# battery_monitor_6803-2_Rev4.net
KiCad netlist of a schematic drawn in EAGLE
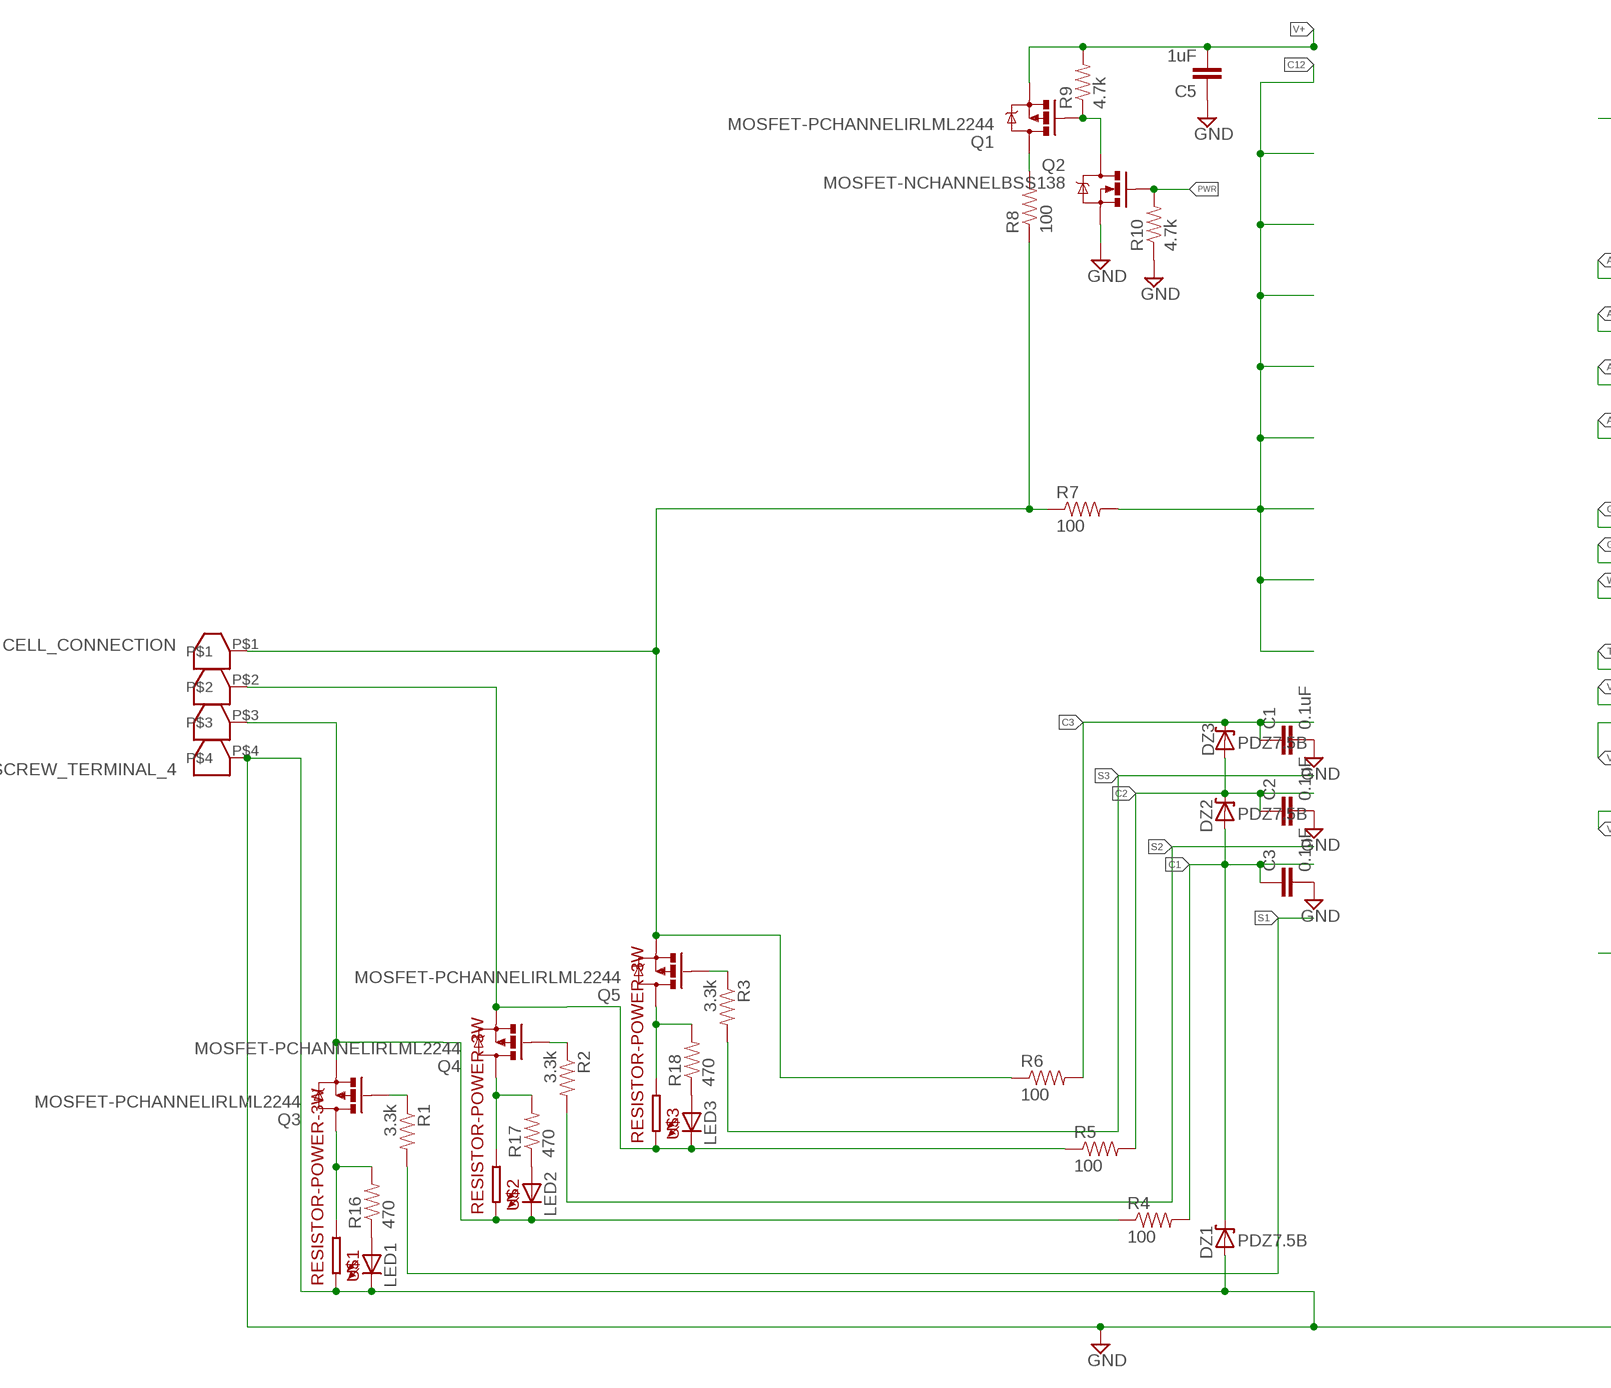
[diagram p0: schematic, sheet 1, part 1 of 2]
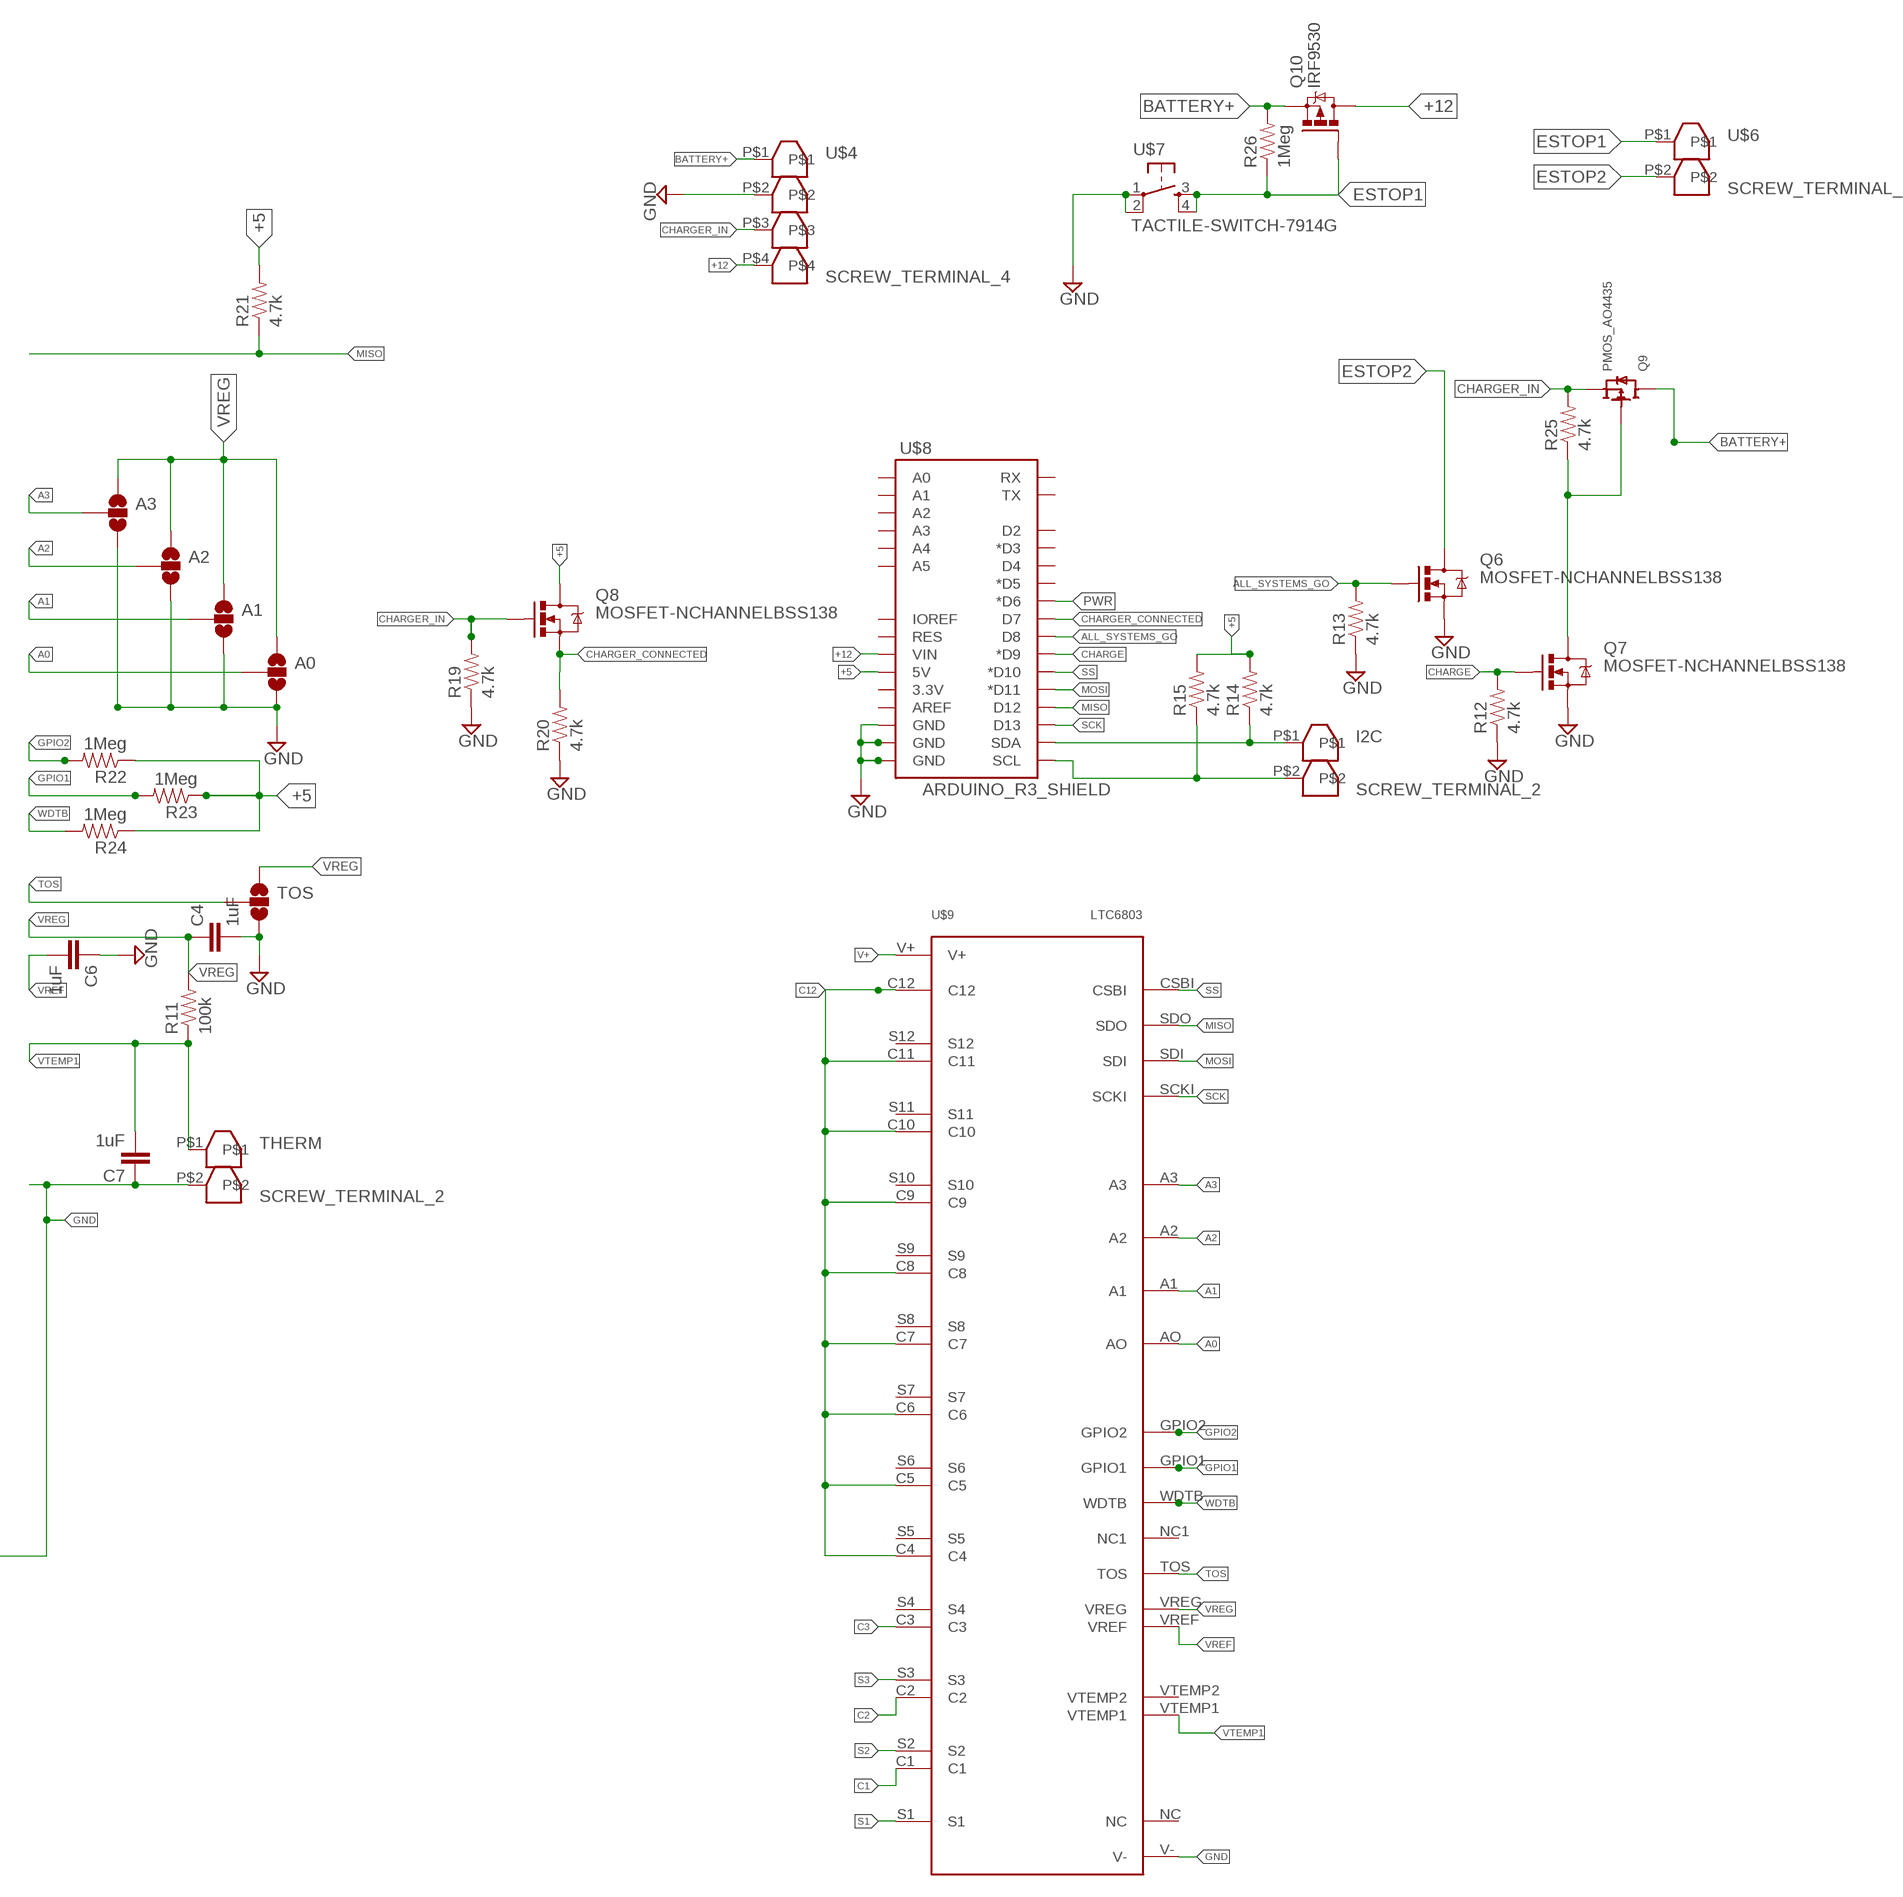
[diagram p1: schematic, sheet 1, part 2 of 2]

(export (version "E")
  (design (tool "Eeschema 10.0.6"))
  (components
    (comp (ref "A0")
      (value "SOLDERJUMPER_2WAYS")
      (footprint "eagle-import:SJ_3")
      (libsource (lib "eagle-import") (part "SOLDERJUMPER_2WAYS"))
    )
    (comp (ref "A1")
      (value "SOLDERJUMPER_2WAYS")
      (footprint "eagle-import:SJ_3")
      (libsource (lib "eagle-import") (part "SOLDERJUMPER_2WAYS"))
    )
    (comp (ref "A2")
      (value "SOLDERJUMPER_2WAYS")
      (footprint "eagle-import:SJ_3")
      (libsource (lib "eagle-import") (part "SOLDERJUMPER_2WAYS"))
    )
    (comp (ref "A3")
      (value "SOLDERJUMPER_2WAYS")
      (footprint "eagle-import:SJ_3")
      (libsource (lib "eagle-import") (part "SOLDERJUMPER_2WAYS"))
    )
    (comp (ref "C1")
      (value "0.1uF")
      (footprint "eagle-import:0603-CAP")
      (fields (field (name "MF") "AVX CORPORATION") (field (name "MPN") "0603YG104ZAT2A"))
      (libsource (lib "eagle-import") (part "0.1UF-100V-10%(0603)"))
    )
    (comp (ref "C2")
      (value "0.1uF")
      (footprint "eagle-import:0603-CAP")
      (fields (field (name "MF") "AVX CORPORATION") (field (name "MPN") "0603YG104ZAT2A"))
      (libsource (lib "eagle-import") (part "0.1UF-100V-10%(0603)"))
    )
    (comp (ref "C3")
      (value "0.1uF")
      (footprint "eagle-import:0603-CAP")
      (fields (field (name "MF") "AVX CORPORATION") (field (name "MPN") "0603YG104ZAT2A"))
      (libsource (lib "eagle-import") (part "0.1UF-100V-10%(0603)"))
    )
    (comp (ref "C4")
      (value "1uF")
      (footprint "eagle-import:0603-CAP")
      (fields (field (name "MPN") "C0603X5R0J105M030BC") (field (name "PROD_ID") "CAP-08390"))
      (libsource (lib "eagle-import") (part "0.1UF-100V-10%(0603)"))
    )
    (comp (ref "C5")
      (value "1uF")
      (footprint "eagle-import:0603-CAP")
      (fields (field (name "MPN") "C0603X5R0J105M030BC") (field (name "PROD_ID") "CAP-08390"))
      (libsource (lib "eagle-import") (part "0.1UF-100V-10%(0603)"))
    )
    (comp (ref "C6")
      (value "1uF")
      (footprint "eagle-import:0603-CAP")
      (fields (field (name "MPN") "C0603X5R0J105M030BC") (field (name "PROD_ID") "CAP-08390"))
      (libsource (lib "eagle-import") (part "0.1UF-100V-10%(0603)"))
    )
    (comp (ref "C7")
      (value "1uF")
      (footprint "eagle-import:0603-CAP")
      (fields (field (name "MPN") "C0603X5R0J105M030BC") (field (name "PROD_ID") "CAP-08390"))
      (libsource (lib "eagle-import") (part "0.1UF-100V-10%(0603)"))
    )
    (comp (ref "CELL_CONNECTION")
      (value "SCREW_TERMINAL_4")
      (footprint "eagle-import:SCREW_TERMINAL_4")
      (fields (field (name "MF") "TYCO ELECTRONICS") (field (name "MPN") "282834-4"))
      (libsource (lib "eagle-import") (part "SCREW_TERMINAL_4"))
    )
    (comp (ref "DZ1")
      (value "PDZ7.5B")
      (footprint "eagle-import:SOD-323")
      (fields (field (name "MPN") "PDZ7.5B,115"))
      (libsource (lib "eagle-import") (part "DIODE-ZENER-BZT52"))
    )
    (comp (ref "DZ2")
      (value "PDZ7.5B")
      (footprint "eagle-import:SOD-323")
      (fields (field (name "MPN") "PDZ7.5B,115"))
      (libsource (lib "eagle-import") (part "DIODE-ZENER-BZT52"))
    )
    (comp (ref "DZ3")
      (value "PDZ7.5B")
      (footprint "eagle-import:SOD-323")
      (fields (field (name "MPN") "PDZ7.5B,115"))
      (libsource (lib "eagle-import") (part "DIODE-ZENER-BZT52"))
    )
    (comp (ref "I2C")
      (value "SCREW_TERMINAL_2")
      (footprint "eagle-import:SCREW_TERMINAL_2")
      (fields (field (name "MF") "TYCO ELECTRONICS") (field (name "MPN") "282834-2"))
      (libsource (lib "eagle-import") (part "isaac1_SCREW_TERMINAL_2"))
    )
    (comp (ref "LED1")
      (value "LED0603")
      (footprint "eagle-import:LED-0603")
      (fields (field (name "MPN") "150060RS75000"))
      (libsource (lib "eagle-import") (part "LED0603"))
    )
    (comp (ref "LED2")
      (value "LED0603")
      (footprint "eagle-import:LED-0603")
      (fields (field (name "MPN") "150060RS75000"))
      (libsource (lib "eagle-import") (part "LED0603"))
    )
    (comp (ref "LED3")
      (value "LED0603")
      (footprint "eagle-import:LED-0603")
      (fields (field (name "MPN") "150060RS75000"))
      (libsource (lib "eagle-import") (part "LED0603"))
    )
    (comp (ref "Q1")
      (value "MOSFET-PCHANNELIRLML2244")
      (footprint "eagle-import:SOT23-3")
      (fields (field (name "MPN") "IRLML2244TRPBF"))
      (libsource (lib "eagle-import") (part "MOSFET-PCHANNELIRLML2244"))
    )
    (comp (ref "Q2")
      (value "MOSFET-NCHANNELBSS138")
      (footprint "eagle-import:SOT23")
      (fields (field (name "MPN") "IRLML0030TRPBF"))
      (libsource (lib "eagle-import") (part "MOSFET-NCHANNELBSS138"))
    )
    (comp (ref "Q3")
      (value "MOSFET-PCHANNELIRLML2244")
      (footprint "eagle-import:SOT23-3")
      (fields (field (name "MPN") "IRLML2244TRPBF"))
      (libsource (lib "eagle-import") (part "MOSFET-PCHANNELIRLML2244"))
    )
    (comp (ref "Q4")
      (value "MOSFET-PCHANNELIRLML2244")
      (footprint "eagle-import:SOT23-3")
      (fields (field (name "MPN") "IRLML2244TRPBF"))
      (libsource (lib "eagle-import") (part "MOSFET-PCHANNELIRLML2244"))
    )
    (comp (ref "Q5")
      (value "MOSFET-PCHANNELIRLML2244")
      (footprint "eagle-import:SOT23-3")
      (fields (field (name "MPN") "IRLML2244TRPBF"))
      (libsource (lib "eagle-import") (part "MOSFET-PCHANNELIRLML2244"))
    )
    (comp (ref "Q6")
      (value "MOSFET-NCHANNELBSS138")
      (footprint "eagle-import:SOT23")
      (fields (field (name "MPN") "IRLML0030TRPBF"))
      (libsource (lib "eagle-import") (part "MOSFET-NCHANNELBSS138"))
    )
    (comp (ref "Q7")
      (value "MOSFET-NCHANNELBSS138")
      (footprint "eagle-import:SOT23")
      (fields (field (name "MPN") "IRLML0030TRPBF"))
      (libsource (lib "eagle-import") (part "MOSFET-NCHANNELBSS138"))
    )
    (comp (ref "Q8")
      (value "MOSFET-NCHANNELBSS138")
      (footprint "eagle-import:SOT23")
      (fields (field (name "MPN") "IRLML0030TRPBF") (field (name "PROD_ID") "TRANS-00830"))
      (libsource (lib "eagle-import") (part "MOSFET-NCHANNELBSS138"))
    )
    (comp (ref "Q9")
      (value "PMOS_AO4435")
      (footprint "eagle-import:SOIC8")
      (fields (field (name "MPN") "SI9407BDY-T1-GE3"))
      (libsource (lib "eagle-import") (part "PMOS_AO4435"))
    )
    (comp (ref "Q10")
      (value "IRF9530")
      (footprint "eagle-import:TO220BV")
      (fields (field (name "MPN") "NTE2383"))
      (libsource (lib "eagle-import") (part "IRF9530"))
    )
    (comp (ref "R1")
      (value "3.3k")
      (footprint "eagle-import:0603-RES")
      (fields (field (name "MF") "VISHAY/DALE") (field (name "MPN") "CRCW06033K00FKEA"))
      (libsource (lib "eagle-import") (part "3.3KOHM1/10W1%(0603)"))
    )
    (comp (ref "R2")
      (value "3.3k")
      (footprint "eagle-import:0603-RES")
      (fields (field (name "MF") "VISHAY/DALE") (field (name "MPN") "CRCW06033K00FKEA"))
      (libsource (lib "eagle-import") (part "3.3KOHM1/10W1%(0603)"))
    )
    (comp (ref "R3")
      (value "3.3k")
      (footprint "eagle-import:0603-RES")
      (fields (field (name "MF") "VISHAY/DALE") (field (name "MPN") "CRCW06033K00FKEA"))
      (libsource (lib "eagle-import") (part "3.3KOHM1/10W1%(0603)"))
    )
    (comp (ref "R4")
      (value "100")
      (footprint "eagle-import:0603-RES")
      (fields (field (name "MPN") "ERJ-1GNF1000C"))
      (libsource (lib "eagle-import") (part "3.3KOHM1/10W1%(0603)"))
    )
    (comp (ref "R5")
      (value "100")
      (footprint "eagle-import:0603-RES")
      (fields (field (name "MPN") "ERJ-1GNF1000C"))
      (libsource (lib "eagle-import") (part "3.3KOHM1/10W1%(0603)"))
    )
    (comp (ref "R6")
      (value "100")
      (footprint "eagle-import:0603-RES")
      (fields (field (name "MPN") "ERJ-1GNF1000C"))
      (libsource (lib "eagle-import") (part "3.3KOHM1/10W1%(0603)"))
    )
    (comp (ref "R7")
      (value "100")
      (footprint "eagle-import:0603-RES")
      (fields (field (name "MPN") "ERJ-1GNF1000C"))
      (libsource (lib "eagle-import") (part "3.3KOHM1/10W1%(0603)"))
    )
    (comp (ref "R8")
      (value "100")
      (footprint "eagle-import:0603-RES")
      (fields (field (name "MPN") "ERJ-1GNF1000C"))
      (libsource (lib "eagle-import") (part "3.3KOHM1/10W1%(0603)"))
    )
    (comp (ref "R9")
      (value "4.7k")
      (footprint "eagle-import:0603-RES")
      (fields (field (name "MF") "VISHAY/DALE") (field (name "MPN") "CRCW06034K70FKEA"))
      (libsource (lib "eagle-import") (part "3.3KOHM1/10W1%(0603)"))
    )
    (comp (ref "R10")
      (value "4.7k")
      (footprint "eagle-import:0603-RES")
      (fields (field (name "MF") "VISHAY/DALE") (field (name "MPN") "CRCW06034K70FKEA"))
      (libsource (lib "eagle-import") (part "3.3KOHM1/10W1%(0603)"))
    )
    (comp (ref "R11")
      (value "100k")
      (footprint "eagle-import:0603-RES")
      (fields (field (name "MF") "FARNELL") (field (name "MPN") "MC0063W06035100K"))
      (libsource (lib "eagle-import") (part "3.3KOHM1/10W1%(0603)"))
    )
    (comp (ref "R12")
      (value "4.7k")
      (footprint "eagle-import:0603-RES")
      (fields (field (name "MF") "VISHAY/DALE") (field (name "MPN") "CRCW06034K70FKEA"))
      (libsource (lib "eagle-import") (part "3.3KOHM1/10W1%(0603)"))
    )
    (comp (ref "R13")
      (value "4.7k")
      (footprint "eagle-import:0603-RES")
      (fields (field (name "MF") "VISHAY/DALE") (field (name "MPN") "CRCW06034K70FKEA"))
      (libsource (lib "eagle-import") (part "3.3KOHM1/10W1%(0603)"))
    )
    (comp (ref "R14")
      (value "4.7k")
      (footprint "eagle-import:0603-RES")
      (fields (field (name "MF") "VISHAY/DALE") (field (name "MPN") "CRCW06034K70FKEA"))
      (libsource (lib "eagle-import") (part "3.3KOHM1/10W1%(0603)"))
    )
    (comp (ref "R15")
      (value "4.7k")
      (footprint "eagle-import:0603-RES")
      (fields (field (name "MF") "VISHAY/DALE") (field (name "MPN") "CRCW06034K70FKEA"))
      (libsource (lib "eagle-import") (part "3.3KOHM1/10W1%(0603)"))
    )
    (comp (ref "R16")
      (value "470")
      (footprint "eagle-import:0603-RES")
      (fields (field (name "MPN") "ERJ-P03F4700V") (field (name "PROD_ID") "RES-07851"))
      (libsource (lib "eagle-import") (part "3.3KOHM1/10W1%(0603)"))
    )
    (comp (ref "R17")
      (value "470")
      (footprint "eagle-import:0603-RES")
      (fields (field (name "MPN") "ERJ-P03F4700V") (field (name "PROD_ID") "RES-07851"))
      (libsource (lib "eagle-import") (part "3.3KOHM1/10W1%(0603)"))
    )
    (comp (ref "R18")
      (value "470")
      (footprint "eagle-import:0603-RES")
      (fields (field (name "MPN") "ERJ-P03F4700V") (field (name "PROD_ID") "RES-07851"))
      (libsource (lib "eagle-import") (part "3.3KOHM1/10W1%(0603)"))
    )
    (comp (ref "R19")
      (value "4.7k")
      (footprint "eagle-import:0603-RES")
      (fields
        (field (name "MF") "VISHAY/DALE")
        (field (name "MPN") "CRCW06034K70FKEA")
        (field (name "PROD_ID") "RES-07851")
      )
      (libsource (lib "eagle-import") (part "3.3KOHM1/10W1%(0603)"))
    )
    (comp (ref "R20")
      (value "4.7k")
      (footprint "eagle-import:0603-RES")
      (fields
        (field (name "MF") "VISHAY/DALE")
        (field (name "MPN") "CRCW06034K70FKEA")
        (field (name "PROD_ID") "RES-07851")
      )
      (libsource (lib "eagle-import") (part "3.3KOHM1/10W1%(0603)"))
    )
    (comp (ref "R21")
      (value "4.7k")
      (footprint "eagle-import:0603-RES")
      (fields
        (field (name "MF") "VISHAY/DALE")
        (field (name "MPN") "CRCW06034K70FKEA")
        (field (name "PROD_ID") "RES-07851")
      )
      (libsource (lib "eagle-import") (part "3.3KOHM1/10W1%(0603)"))
    )
    (comp (ref "R22")
      (value "1Meg")
      (footprint "eagle-import:0603-RES")
      (fields (field (name "MPN") "ERJ-3EKF1004V") (field (name "PROD_ID") "RES-07851"))
      (libsource (lib "eagle-import") (part "3.3KOHM1/10W1%(0603)"))
    )
    (comp (ref "R23")
      (value "1Meg")
      (footprint "eagle-import:0603-RES")
      (fields (field (name "MPN") "ERJ-3EKF1004V") (field (name "PROD_ID") "RES-07851"))
      (libsource (lib "eagle-import") (part "3.3KOHM1/10W1%(0603)"))
    )
    (comp (ref "R24")
      (value "1Meg")
      (footprint "eagle-import:0603-RES")
      (fields (field (name "MPN") "ERJ-3EKF1004V") (field (name "PROD_ID") "RES-07851"))
      (libsource (lib "eagle-import") (part "3.3KOHM1/10W1%(0603)"))
    )
    (comp (ref "R25")
      (value "4.7k")
      (footprint "eagle-import:0603-RES")
      (fields
        (field (name "MF") "VISHAY/DALE")
        (field (name "MPN") "CRCW06034K70FKEA")
        (field (name "PROD_ID") "RES-07851")
      )
      (libsource (lib "eagle-import") (part "3.3KOHM1/10W1%(0603)"))
    )
    (comp (ref "R26")
      (value "1Meg")
      (footprint "eagle-import:0603-RES")
      (fields (field (name "MPN") "ERJ-3EKF1004V"))
      (libsource (lib "eagle-import") (part "3.3KOHM1/10W1%(0603)"))
    )
    (comp (ref "THERM")
      (value "SCREW_TERMINAL_2")
      (footprint "eagle-import:SCREW_TERMINAL_2")
      (fields (field (name "MF") "TYCO ELECTRONICS") (field (name "MPN") "282834-2"))
      (libsource (lib "eagle-import") (part "isaac1_SCREW_TERMINAL_2"))
    )
    (comp (ref "TOS")
      (value "SOLDERJUMPER_2WAYS")
      (footprint "eagle-import:SJ_3")
      (libsource (lib "eagle-import") (part "SOLDERJUMPER_2WAYS"))
    )
    (comp (ref "U$1")
      (value "RESISTOR-POWER-3W")
      (footprint "eagle-import:RESISTOR-3W")
      (fields (field (name "MPN") "ERG-3SJ200"))
      (libsource (lib "eagle-import") (part "RESISTOR-POWER-3W"))
    )
    (comp (ref "U$2")
      (value "RESISTOR-POWER-3W")
      (footprint "eagle-import:RESISTOR-3W")
      (fields (field (name "MPN") "ERG-3SJ200"))
      (libsource (lib "eagle-import") (part "RESISTOR-POWER-3W"))
    )
    (comp (ref "U$3")
      (value "RESISTOR-POWER-3W")
      (footprint "eagle-import:RESISTOR-3W")
      (fields (field (name "MPN") "ERG-3SJ200"))
      (libsource (lib "eagle-import") (part "RESISTOR-POWER-3W"))
    )
    (comp (ref "U$4")
      (value "SCREW_TERMINAL_4")
      (footprint "eagle-import:SCREW_TERMINAL_4")
      (fields (field (name "MF") "TYCO ELECTRONICS") (field (name "MPN") "282834-4"))
      (libsource (lib "eagle-import") (part "SCREW_TERMINAL_4"))
    )
    (comp (ref "U$6")
      (value "SCREW_TERMINAL_2")
      (footprint "eagle-import:SCREW_TERMINAL_2")
      (fields (field (name "MF") "TYCO ELECTRONICS") (field (name "MPN") "282834-2"))
      (libsource (lib "eagle-import") (part "SCREW_TERMINAL_2"))
    )
    (comp (ref "U$7")
      (value "TACTILE-SWITCH-7914G")
      (footprint "eagle-import:7914G")
      (fields (field (name "MF") "BOURNS, INC.") (field (name "MPN") "7914G-1-000E"))
      (libsource (lib "eagle-import") (part "TACTILE-SWITCH-7914G"))
    )
    (comp (ref "U$8")
      (value "ARDUINO_R3_SHIELD")
      (footprint "eagle-import:UNO_R3_SHIELD")
      (libsource (lib "eagle-import") (part "ARDUINO_R3_SHIELD"))
    )
    (comp (ref "U$9")
      (value "LTC6803")
      (footprint "eagle-import:LTC6803_BREAKOUT")
      (fields (field (name "MPN") "LTC6803IG-2#PBF"))
      (libsource (lib "eagle-import") (part "LTC6803_BREAKOUT"))
    )
  )
  (nets
    (net (code "1") (name "+5") (class "Default")
      (node (ref "Q8") (pin "3") (pinfunction "D_3") (pintype "passive"))
      (node (ref "R14") (pin "2") (pinfunction "2_2") (pintype "passive"))
      (node (ref "R15") (pin "2") (pinfunction "2_2") (pintype "passive"))
      (node (ref "R21") (pin "2") (pinfunction "2_2") (pintype "passive"))
      (node (ref "R22") (pin "1") (pinfunction "1_1") (pintype "passive"))
      (node (ref "R23") (pin "1") (pinfunction "1_1") (pintype "passive"))
      (node (ref "R24") (pin "1") (pinfunction "1_1") (pintype "passive"))
      (node (ref "U$8") (pin "5V") (pinfunction "5V_5V") (pintype "bidirectional"))
    )
    (net (code "2") (name "+12") (class "Default")
      (node (ref "Q10") (pin "D") (pinfunction "D_D") (pintype "passive"))
      (node (ref "U$4") (pin "P$4") (pinfunction "P$4_P$4") (pintype "bidirectional"))
      (node (ref "U$8") (pin "VIN") (pinfunction "VIN_VIN") (pintype "bidirectional"))
    )
    (net (code "3") (name "A0") (class "Default")
      (node (ref "A0") (pin "2") (pinfunction "2_2") (pintype "passive"))
      (node (ref "U$9") (pin "AO") (pinfunction "AO_AO") (pintype "bidirectional"))
    )
    (net (code "4") (name "A1") (class "Default")
      (node (ref "A1") (pin "2") (pinfunction "2_2") (pintype "passive"))
      (node (ref "U$9") (pin "A1") (pinfunction "A1_A1") (pintype "bidirectional"))
    )
    (net (code "5") (name "A2") (class "Default")
      (node (ref "A2") (pin "2") (pinfunction "2_2") (pintype "passive"))
      (node (ref "U$9") (pin "A2") (pinfunction "A2_A2") (pintype "bidirectional"))
    )
    (net (code "6") (name "A3") (class "Default")
      (node (ref "A3") (pin "2") (pinfunction "2_2") (pintype "passive"))
      (node (ref "U$9") (pin "A3") (pinfunction "A3_A3") (pintype "bidirectional"))
    )
    (net (code "7") (name "ALL_SYSTEMS_GO") (class "Default")
      (node (ref "Q6") (pin "1") (pinfunction "G_1") (pintype "passive"))
      (node (ref "R13") (pin "2") (pinfunction "2_2") (pintype "passive"))
      (node (ref "U$8") (pin "D8") (pinfunction "D8_D8") (pintype "bidirectional"))
    )
    (net (code "8") (name "BATTERY+") (class "Default")
      (node (ref "Q10") (pin "S") (pinfunction "S_S") (pintype "passive"))
      (node (ref "Q9") (pin "5") (pinfunction "DRAIN_5") (pintype "bidirectional"))
      (node (ref "Q9") (pin "6") (pinfunction "DRAIN_6") (pintype "bidirectional"))
      (node (ref "Q9") (pin "7") (pinfunction "DRAIN_7") (pintype "bidirectional"))
      (node (ref "Q9") (pin "8") (pinfunction "DRAIN_8") (pintype "bidirectional"))
      (node (ref "R26") (pin "2") (pinfunction "2_2") (pintype "passive"))
      (node (ref "U$4") (pin "P$1") (pinfunction "P$1_P$1") (pintype "bidirectional"))
    )
    (net (code "9") (name "C1") (class "Default")
      (node (ref "C3") (pin "1") (pinfunction "1_1") (pintype "passive"))
      (node (ref "DZ1") (pin "1") (pinfunction "C_1") (pintype "passive"))
      (node (ref "DZ2") (pin "2") (pinfunction "A_2") (pintype "passive"))
      (node (ref "R4") (pin "2") (pinfunction "2_2") (pintype "passive"))
      (node (ref "U$9") (pin "C1") (pinfunction "C1_C1") (pintype "bidirectional"))
    )
    (net (code "10") (name "C2") (class "Default")
      (node (ref "C2") (pin "1") (pinfunction "1_1") (pintype "passive"))
      (node (ref "DZ2") (pin "1") (pinfunction "C_1") (pintype "passive"))
      (node (ref "DZ3") (pin "2") (pinfunction "A_2") (pintype "passive"))
      (node (ref "R5") (pin "2") (pinfunction "2_2") (pintype "passive"))
      (node (ref "U$9") (pin "C2") (pinfunction "C2_C2") (pintype "bidirectional"))
    )
    (net (code "11") (name "C3") (class "Default")
      (node (ref "C1") (pin "1") (pinfunction "1_1") (pintype "passive"))
      (node (ref "DZ3") (pin "1") (pinfunction "C_1") (pintype "passive"))
      (node (ref "R6") (pin "2") (pinfunction "2_2") (pintype "passive"))
      (node (ref "U$9") (pin "C3") (pinfunction "C3_C3") (pintype "bidirectional"))
    )
    (net (code "12") (name "C12") (class "Default")
      (node (ref "R7") (pin "2") (pinfunction "2_2") (pintype "passive"))
      (node (ref "U$9") (pin "C10") (pinfunction "C10_C10") (pintype "bidirectional"))
      (node (ref "U$9") (pin "C11") (pinfunction "C11_C11") (pintype "bidirectional"))
      (node (ref "U$9") (pin "C12") (pinfunction "C12_C12") (pintype "bidirectional"))
      (node (ref "U$9") (pin "C4") (pinfunction "C4_C4") (pintype "bidirectional"))
      (node (ref "U$9") (pin "C5") (pinfunction "C5_C5") (pintype "bidirectional"))
      (node (ref "U$9") (pin "C6") (pinfunction "C6_C6") (pintype "bidirectional"))
      (node (ref "U$9") (pin "C7") (pinfunction "C7_C7") (pintype "bidirectional"))
      (node (ref "U$9") (pin "C8") (pinfunction "C8_C8") (pintype "bidirectional"))
      (node (ref "U$9") (pin "C9") (pinfunction "C9_C9") (pintype "bidirectional"))
    )
    (net (code "13") (name "CHARGE") (class "Default")
      (node (ref "Q7") (pin "1") (pinfunction "G_1") (pintype "passive"))
      (node (ref "R12") (pin "2") (pinfunction "2_2") (pintype "passive"))
      (node (ref "U$8") (pin "D9") (pinfunction "*D9_D9") (pintype "bidirectional"))
    )
    (net (code "14") (name "CHARGER_CONNECTED") (class "Default")
      (node (ref "Q8") (pin "2") (pinfunction "S_2") (pintype "passive"))
      (node (ref "R20") (pin "2") (pinfunction "2_2") (pintype "passive"))
      (node (ref "U$8") (pin "D7") (pinfunction "D7_D7") (pintype "bidirectional"))
    )
    (net (code "15") (name "CHARGER_IN") (class "Default")
      (node (ref "Q8") (pin "1") (pinfunction "G_1") (pintype "passive"))
      (node (ref "Q9") (pin "1") (pinfunction "SOURCE_1") (pintype "bidirectional"))
      (node (ref "Q9") (pin "2") (pinfunction "SOURCE_2") (pintype "bidirectional"))
      (node (ref "Q9") (pin "3") (pinfunction "SOURCE_3") (pintype "bidirectional"))
      (node (ref "R19") (pin "2") (pinfunction "2_2") (pintype "passive"))
      (node (ref "R25") (pin "2") (pinfunction "2_2") (pintype "passive"))
      (node (ref "U$4") (pin "P$3") (pinfunction "P$3_P$3") (pintype "bidirectional"))
    )
    (net (code "16") (name "ESTOP1") (class "Default")
      (node (ref "Q10") (pin "G") (pinfunction "G_G") (pintype "passive"))
      (node (ref "R26") (pin "1") (pinfunction "1_1") (pintype "passive"))
      (node (ref "U$6") (pin "P$1") (pinfunction "P$1_P$1") (pintype "bidirectional"))
      (node (ref "U$7") (pin "3") (pinfunction "3_3") (pintype "passive"))
      (node (ref "U$7") (pin "4") (pinfunction "4_4") (pintype "passive"))
    )
    (net (code "17") (name "ESTOP2") (class "Default")
      (node (ref "Q6") (pin "3") (pinfunction "D_3") (pintype "passive"))
      (node (ref "U$6") (pin "P$2") (pinfunction "P$2_P$2") (pintype "bidirectional"))
    )
    (net (code "18") (name "GND") (class "Default")
      (node (ref "A0") (pin "3") (pinfunction "3_3") (pintype "passive"))
      (node (ref "A1") (pin "3") (pinfunction "3_3") (pintype "passive"))
      (node (ref "A2") (pin "3") (pinfunction "3_3") (pintype "passive"))
      (node (ref "A3") (pin "3") (pinfunction "3_3") (pintype "passive"))
      (node (ref "C1") (pin "2") (pinfunction "2_2") (pintype "passive"))
      (node (ref "C2") (pin "2") (pinfunction "2_2") (pintype "passive"))
      (node (ref "C3") (pin "2") (pinfunction "2_2") (pintype "passive"))
      (node (ref "C4") (pin "2") (pinfunction "2_2") (pintype "passive"))
      (node (ref "C5") (pin "1") (pinfunction "1_1") (pintype "passive"))
      (node (ref "C6") (pin "1") (pinfunction "1_1") (pintype "passive"))
      (node (ref "C7") (pin "1") (pinfunction "1_1") (pintype "passive"))
      (node (ref "CELL_CONNECTION") (pin "P$4") (pinfunction "P$4_P$4") (pintype "bidirectional"))
      (node (ref "DZ1") (pin "2") (pinfunction "A_2") (pintype "passive"))
      (node (ref "LED1") (pin "C") (pinfunction "C_C") (pintype "passive"))
      (node (ref "Q2") (pin "2") (pinfunction "S_2") (pintype "passive"))
      (node (ref "Q6") (pin "2") (pinfunction "S_2") (pintype "passive"))
      (node (ref "Q7") (pin "2") (pinfunction "S_2") (pintype "passive"))
      (node (ref "R10") (pin "1") (pinfunction "1_1") (pintype "passive"))
      (node (ref "R12") (pin "1") (pinfunction "1_1") (pintype "passive"))
      (node (ref "R13") (pin "1") (pinfunction "1_1") (pintype "passive"))
      (node (ref "R19") (pin "1") (pinfunction "1_1") (pintype "passive"))
      (node (ref "R20") (pin "1") (pinfunction "1_1") (pintype "passive"))
      (node (ref "THERM") (pin "P$2") (pinfunction "P$2_P$2") (pintype "bidirectional"))
      (node (ref "TOS") (pin "3") (pinfunction "3_3") (pintype "passive"))
      (node (ref "U$1") (pin "P$2") (pinfunction "P$2_P$2") (pintype "bidirectional"))
      (node (ref "U$4") (pin "P$2") (pinfunction "P$2_P$2") (pintype "bidirectional"))
      (node (ref "U$7") (pin "1") (pinfunction "1_1") (pintype "passive"))
      (node (ref "U$7") (pin "2") (pinfunction "2_2") (pintype "passive"))
      (node (ref "U$8") (pin "GND@0") (pinfunction "GND_GND@0") (pintype "bidirectional"))
      (node (ref "U$8") (pin "GND@1") (pinfunction "GND_GND@1") (pintype "bidirectional"))
      (node (ref "U$8") (pin "GND@2") (pinfunction "GND_GND@2") (pintype "bidirectional"))
      (node (ref "U$9") (pin "V-") (pinfunction "V-_V-") (pintype "bidirectional"))
    )
    (net (code "19") (name "GPIO1") (class "Default")
      (node (ref "R23") (pin "2") (pinfunction "2_2") (pintype "passive"))
      (node (ref "U$9") (pin "GPIO1") (pinfunction "GPIO1_GPIO1") (pintype "bidirectional"))
    )
    (net (code "20") (name "GPIO2") (class "Default")
      (node (ref "R22") (pin "2") (pinfunction "2_2") (pintype "passive"))
      (node (ref "U$9") (pin "GPIO2") (pinfunction "GPIO2_GPIO2") (pintype "bidirectional"))
    )
    (net (code "21") (name "MISO") (class "Default")
      (node (ref "R21") (pin "1") (pinfunction "1_1") (pintype "passive"))
      (node (ref "U$8") (pin "D12") (pinfunction "D12_D12") (pintype "bidirectional"))
      (node (ref "U$9") (pin "SDO") (pinfunction "SDO_SDO") (pintype "bidirectional"))
    )
    (net (code "22") (name "MOSI") (class "Default")
      (node (ref "U$8") (pin "D11") (pinfunction "*D11_D11") (pintype "bidirectional"))
      (node (ref "U$9") (pin "SDI") (pinfunction "SDI_SDI") (pintype "bidirectional"))
    )
    (net (code "23") (name "Net-(I2C-PadP$1)") (class "Default")
      (node (ref "I2C") (pin "P$1") (pinfunction "P$1_P$1") (pintype "bidirectional"))
      (node (ref "R14") (pin "1") (pinfunction "1_1") (pintype "passive"))
      (node (ref "U$8") (pin "SDA") (pinfunction "SDA_SDA") (pintype "bidirectional"))
    )
    (net (code "24") (name "Net-(I2C-PadP$2)") (class "Default")
      (node (ref "I2C") (pin "P$2") (pinfunction "P$2_P$2") (pintype "bidirectional"))
      (node (ref "R15") (pin "1") (pinfunction "1_1") (pintype "passive"))
      (node (ref "U$8") (pin "SCL") (pinfunction "SCL_SCL") (pintype "bidirectional"))
    )
    (net (code "25") (name "Net-(LED1-PadA)") (class "Default")
      (node (ref "LED1") (pin "A") (pinfunction "A_A") (pintype "passive"))
      (node (ref "R16") (pin "1") (pinfunction "1_1") (pintype "passive"))
    )
    (net (code "26") (name "Net-(LED2-PadA)") (class "Default")
      (node (ref "LED2") (pin "A") (pinfunction "A_A") (pintype "passive"))
      (node (ref "R17") (pin "1") (pinfunction "1_1") (pintype "passive"))
    )
    (net (code "27") (name "Net-(LED3-PadA)") (class "Default")
      (node (ref "LED3") (pin "A") (pinfunction "A_A") (pintype "passive"))
      (node (ref "R18") (pin "1") (pinfunction "1_1") (pintype "passive"))
    )
    (net (code "28") (name "Net-(Q1-D)") (class "Default")
      (node (ref "Q1") (pin "3") (pinfunction "D_3") (pintype "passive"))
      (node (ref "R8") (pin "2") (pinfunction "2_2") (pintype "passive"))
    )
    (net (code "29") (name "Net-(Q1-G)") (class "Default")
      (node (ref "Q1") (pin "1") (pinfunction "G_1") (pintype "passive"))
      (node (ref "Q2") (pin "3") (pinfunction "D_3") (pintype "passive"))
      (node (ref "R9") (pin "1") (pinfunction "1_1") (pintype "passive"))
    )
    (net (code "30") (name "Net-(Q3-D)") (class "Default")
      (node (ref "Q3") (pin "3") (pinfunction "D_3") (pintype "passive"))
      (node (ref "R16") (pin "2") (pinfunction "2_2") (pintype "passive"))
      (node (ref "U$1") (pin "P$1") (pinfunction "P$1_P$1") (pintype "bidirectional"))
    )
    (net (code "31") (name "Net-(Q3-G)") (class "Default")
      (node (ref "Q3") (pin "1") (pinfunction "G_1") (pintype "passive"))
      (node (ref "R1") (pin "1") (pinfunction "1_1") (pintype "passive"))
    )
    (net (code "32") (name "Net-(Q3-S)") (class "Default")
      (node (ref "CELL_CONNECTION") (pin "P$3") (pinfunction "P$3_P$3") (pintype "bidirectional"))
      (node (ref "LED2") (pin "C") (pinfunction "C_C") (pintype "passive"))
      (node (ref "Q3") (pin "2") (pinfunction "S_2") (pintype "passive"))
      (node (ref "R4") (pin "1") (pinfunction "1_1") (pintype "passive"))
      (node (ref "U$2") (pin "P$2") (pinfunction "P$2_P$2") (pintype "bidirectional"))
    )
    (net (code "33") (name "Net-(Q4-D)") (class "Default")
      (node (ref "Q4") (pin "3") (pinfunction "D_3") (pintype "passive"))
      (node (ref "R17") (pin "2") (pinfunction "2_2") (pintype "passive"))
      (node (ref "U$2") (pin "P$1") (pinfunction "P$1_P$1") (pintype "bidirectional"))
    )
    (net (code "34") (name "Net-(Q4-G)") (class "Default")
      (node (ref "Q4") (pin "1") (pinfunction "G_1") (pintype "passive"))
      (node (ref "R2") (pin "1") (pinfunction "1_1") (pintype "passive"))
    )
    (net (code "35") (name "Net-(Q4-S)") (class "Default")
      (node (ref "CELL_CONNECTION") (pin "P$2") (pinfunction "P$2_P$2") (pintype "bidirectional"))
      (node (ref "LED3") (pin "C") (pinfunction "C_C") (pintype "passive"))
      (node (ref "Q4") (pin "2") (pinfunction "S_2") (pintype "passive"))
      (node (ref "R5") (pin "1") (pinfunction "1_1") (pintype "passive"))
      (node (ref "U$3") (pin "P$2") (pinfunction "P$2_P$2") (pintype "bidirectional"))
    )
    (net (code "36") (name "Net-(Q5-D)") (class "Default")
      (node (ref "Q5") (pin "3") (pinfunction "D_3") (pintype "passive"))
      (node (ref "R18") (pin "2") (pinfunction "2_2") (pintype "passive"))
      (node (ref "U$3") (pin "P$1") (pinfunction "P$1_P$1") (pintype "bidirectional"))
    )
    (net (code "37") (name "Net-(Q5-G)") (class "Default")
      (node (ref "Q5") (pin "1") (pinfunction "G_1") (pintype "passive"))
      (node (ref "R3") (pin "1") (pinfunction "1_1") (pintype "passive"))
    )
    (net (code "38") (name "Net-(Q5-S)") (class "Default")
      (node (ref "CELL_CONNECTION") (pin "P$1") (pinfunction "P$1_P$1") (pintype "bidirectional"))
      (node (ref "Q5") (pin "2") (pinfunction "S_2") (pintype "passive"))
      (node (ref "R6") (pin "1") (pinfunction "1_1") (pintype "passive"))
      (node (ref "R7") (pin "1") (pinfunction "1_1") (pintype "passive"))
      (node (ref "R8") (pin "1") (pinfunction "1_1") (pintype "passive"))
    )
    (net (code "39") (name "Net-(Q7-D)") (class "Default")
      (node (ref "Q7") (pin "3") (pinfunction "D_3") (pintype "passive"))
      (node (ref "Q9") (pin "4") (pinfunction "GATE_4") (pintype "bidirectional"))
      (node (ref "R25") (pin "1") (pinfunction "1_1") (pintype "passive"))
    )
    (net (code "40") (name "PWR") (class "Default")
      (node (ref "Q2") (pin "1") (pinfunction "G_1") (pintype "passive"))
      (node (ref "R10") (pin "2") (pinfunction "2_2") (pintype "passive"))
      (node (ref "U$8") (pin "D6") (pinfunction "*D6_D6") (pintype "bidirectional"))
    )
    (net (code "41") (name "S1") (class "Default")
      (node (ref "R1") (pin "2") (pinfunction "2_2") (pintype "passive"))
      (node (ref "U$9") (pin "S1") (pinfunction "S1_S1") (pintype "bidirectional"))
    )
    (net (code "42") (name "S2") (class "Default")
      (node (ref "R2") (pin "2") (pinfunction "2_2") (pintype "passive"))
      (node (ref "U$9") (pin "S2") (pinfunction "S2_S2") (pintype "bidirectional"))
    )
    (net (code "43") (name "S3") (class "Default")
      (node (ref "R3") (pin "2") (pinfunction "2_2") (pintype "passive"))
      (node (ref "U$9") (pin "S3") (pinfunction "S3_S3") (pintype "bidirectional"))
    )
    (net (code "44") (name "SCK") (class "Default")
      (node (ref "U$8") (pin "D13") (pinfunction "D13_D13") (pintype "bidirectional"))
      (node (ref "U$9") (pin "SCKI") (pinfunction "SCKI_SCKI") (pintype "bidirectional"))
    )
    (net (code "45") (name "SS") (class "Default")
      (node (ref "U$8") (pin "D10") (pinfunction "*D10_D10") (pintype "bidirectional"))
      (node (ref "U$9") (pin "CSBI") (pinfunction "CSBI_CSBI") (pintype "bidirectional"))
    )
    (net (code "46") (name "TOS") (class "Default")
      (node (ref "TOS") (pin "2") (pinfunction "2_2") (pintype "passive"))
      (node (ref "U$9") (pin "TOS") (pinfunction "TOS_TOS") (pintype "bidirectional"))
    )
    (net (code "47") (name "V+") (class "Default")
      (node (ref "C5") (pin "2") (pinfunction "2_2") (pintype "passive"))
      (node (ref "Q1") (pin "2") (pinfunction "S_2") (pintype "passive"))
      (node (ref "R9") (pin "2") (pinfunction "2_2") (pintype "passive"))
      (node (ref "U$9") (pin "V+") (pinfunction "V+_V+") (pintype "bidirectional"))
    )
    (net (code "48") (name "VREF") (class "Default")
      (node (ref "C6") (pin "2") (pinfunction "2_2") (pintype "passive"))
      (node (ref "U$9") (pin "VREF") (pinfunction "VREF_VREF") (pintype "bidirectional"))
    )
    (net (code "49") (name "VREG") (class "Default")
      (node (ref "A0") (pin "1") (pinfunction "1_1") (pintype "passive"))
      (node (ref "A1") (pin "1") (pinfunction "1_1") (pintype "passive"))
      (node (ref "A2") (pin "1") (pinfunction "1_1") (pintype "passive"))
      (node (ref "A3") (pin "1") (pinfunction "1_1") (pintype "passive"))
      (node (ref "C4") (pin "1") (pinfunction "1_1") (pintype "passive"))
      (node (ref "R11") (pin "2") (pinfunction "2_2") (pintype "passive"))
      (node (ref "TOS") (pin "1") (pinfunction "1_1") (pintype "passive"))
      (node (ref "U$9") (pin "VREG") (pinfunction "VREG_VREG") (pintype "bidirectional"))
    )
    (net (code "50") (name "VTEMP1") (class "Default")
      (node (ref "C7") (pin "2") (pinfunction "2_2") (pintype "passive"))
      (node (ref "R11") (pin "1") (pinfunction "1_1") (pintype "passive"))
      (node (ref "THERM") (pin "P$1") (pinfunction "P$1_P$1") (pintype "bidirectional"))
      (node (ref "U$9") (pin "VTEMP1") (pinfunction "VTEMP1_VTEMP1") (pintype "bidirectional"))
    )
    (net (code "51") (name "WDTB") (class "Default")
      (node (ref "R24") (pin "2") (pinfunction "2_2") (pintype "passive"))
      (node (ref "U$9") (pin "WDTB") (pinfunction "WDTB_WDTB") (pintype "bidirectional"))
    )
    (net (code "52") (name "unconnected-(U$8-*D3-PadD3)") (class "Default")
      (node (ref "U$8") (pin "D3") (pinfunction "*D3_D3") (pintype "bidirectional"))
    )
    (net (code "53") (name "unconnected-(U$8-*D5-PadD5)") (class "Default")
      (node (ref "U$8") (pin "D5") (pinfunction "*D5_D5") (pintype "bidirectional"))
    )
    (net (code "54") (name "unconnected-(U$8-Pad3.3V)") (class "Default")
      (node (ref "U$8") (pin "3.3V") (pinfunction "3.3V_3.3V") (pintype "bidirectional"))
    )
    (net (code "55") (name "unconnected-(U$8-PadA0)") (class "Default")
      (node (ref "U$8") (pin "A0") (pinfunction "A0_A0") (pintype "bidirectional"))
    )
    (net (code "56") (name "unconnected-(U$8-PadA1)") (class "Default")
      (node (ref "U$8") (pin "A1") (pinfunction "A1_A1") (pintype "bidirectional"))
    )
    (net (code "57") (name "unconnected-(U$8-PadA2)") (class "Default")
      (node (ref "U$8") (pin "A2") (pinfunction "A2_A2") (pintype "bidirectional"))
    )
    (net (code "58") (name "unconnected-(U$8-PadA3)") (class "Default")
      (node (ref "U$8") (pin "A3") (pinfunction "A3_A3") (pintype "bidirectional"))
    )
    (net (code "59") (name "unconnected-(U$8-PadA4)") (class "Default")
      (node (ref "U$8") (pin "A4") (pinfunction "A4_A4") (pintype "bidirectional"))
    )
    (net (code "60") (name "unconnected-(U$8-PadA5)") (class "Default")
      (node (ref "U$8") (pin "A5") (pinfunction "A5_A5") (pintype "bidirectional"))
    )
    (net (code "61") (name "unconnected-(U$8-PadAREF)") (class "Default")
      (node (ref "U$8") (pin "AREF") (pinfunction "AREF_AREF") (pintype "bidirectional"))
    )
    (net (code "62") (name "unconnected-(U$8-PadD2)") (class "Default")
      (node (ref "U$8") (pin "D2") (pinfunction "D2_D2") (pintype "bidirectional"))
    )
    (net (code "63") (name "unconnected-(U$8-PadD4)") (class "Default")
      (node (ref "U$8") (pin "D4") (pinfunction "D4_D4") (pintype "bidirectional"))
    )
    (net (code "64") (name "unconnected-(U$8-PadIOREF)") (class "Default")
      (node (ref "U$8") (pin "IOREF") (pinfunction "IOREF_IOREF") (pintype "bidirectional"))
    )
    (net (code "65") (name "unconnected-(U$8-PadRES)") (class "Default")
      (node (ref "U$8") (pin "RES") (pinfunction "RES_RES") (pintype "bidirectional"))
    )
    (net (code "66") (name "unconnected-(U$8-PadRX)") (class "Default")
      (node (ref "U$8") (pin "RX") (pinfunction "RX_RX") (pintype "bidirectional"))
    )
    (net (code "67") (name "unconnected-(U$8-PadTX)") (class "Default")
      (node (ref "U$8") (pin "TX") (pinfunction "TX_TX") (pintype "bidirectional"))
    )
    (net (code "68") (name "unconnected-(U$9-PadNC)") (class "Default")
      (node (ref "U$9") (pin "NC") (pinfunction "NC_NC") (pintype "bidirectional"))
    )
    (net (code "69") (name "unconnected-(U$9-PadNC1)") (class "Default")
      (node (ref "U$9") (pin "NC1") (pinfunction "NC1_NC1") (pintype "bidirectional"))
    )
    (net (code "70") (name "unconnected-(U$9-PadS4)") (class "Default")
      (node (ref "U$9") (pin "S4") (pinfunction "S4_S4") (pintype "bidirectional"))
    )
    (net (code "71") (name "unconnected-(U$9-PadS5)") (class "Default")
      (node (ref "U$9") (pin "S5") (pinfunction "S5_S5") (pintype "bidirectional"))
    )
    (net (code "72") (name "unconnected-(U$9-PadS6)") (class "Default")
      (node (ref "U$9") (pin "S6") (pinfunction "S6_S6") (pintype "bidirectional"))
    )
    (net (code "73") (name "unconnected-(U$9-PadS7)") (class "Default")
      (node (ref "U$9") (pin "S7") (pinfunction "S7_S7") (pintype "bidirectional"))
    )
    (net (code "74") (name "unconnected-(U$9-PadS8)") (class "Default")
      (node (ref "U$9") (pin "S8") (pinfunction "S8_S8") (pintype "bidirectional"))
    )
    (net (code "75") (name "unconnected-(U$9-PadS9)") (class "Default")
      (node (ref "U$9") (pin "S9") (pinfunction "S9_S9") (pintype "bidirectional"))
    )
    (net (code "76") (name "unconnected-(U$9-PadS10)") (class "Default")
      (node (ref "U$9") (pin "S10") (pinfunction "S10_S10") (pintype "bidirectional"))
    )
    (net (code "77") (name "unconnected-(U$9-PadS11)") (class "Default")
      (node (ref "U$9") (pin "S11") (pinfunction "S11_S11") (pintype "bidirectional"))
    )
    (net (code "78") (name "unconnected-(U$9-PadS12)") (class "Default")
      (node (ref "U$9") (pin "S12") (pinfunction "S12_S12") (pintype "bidirectional"))
    )
    (net (code "79") (name "unconnected-(U$9-PadVTEMP2)") (class "Default")
      (node (ref "U$9") (pin "VTEMP2") (pinfunction "VTEMP2_VTEMP2") (pintype "bidirectional"))
    )
  )
)
